# rpi5torpi4.net
KiCad netlist of a schematic drawn in EasyEDA Pro
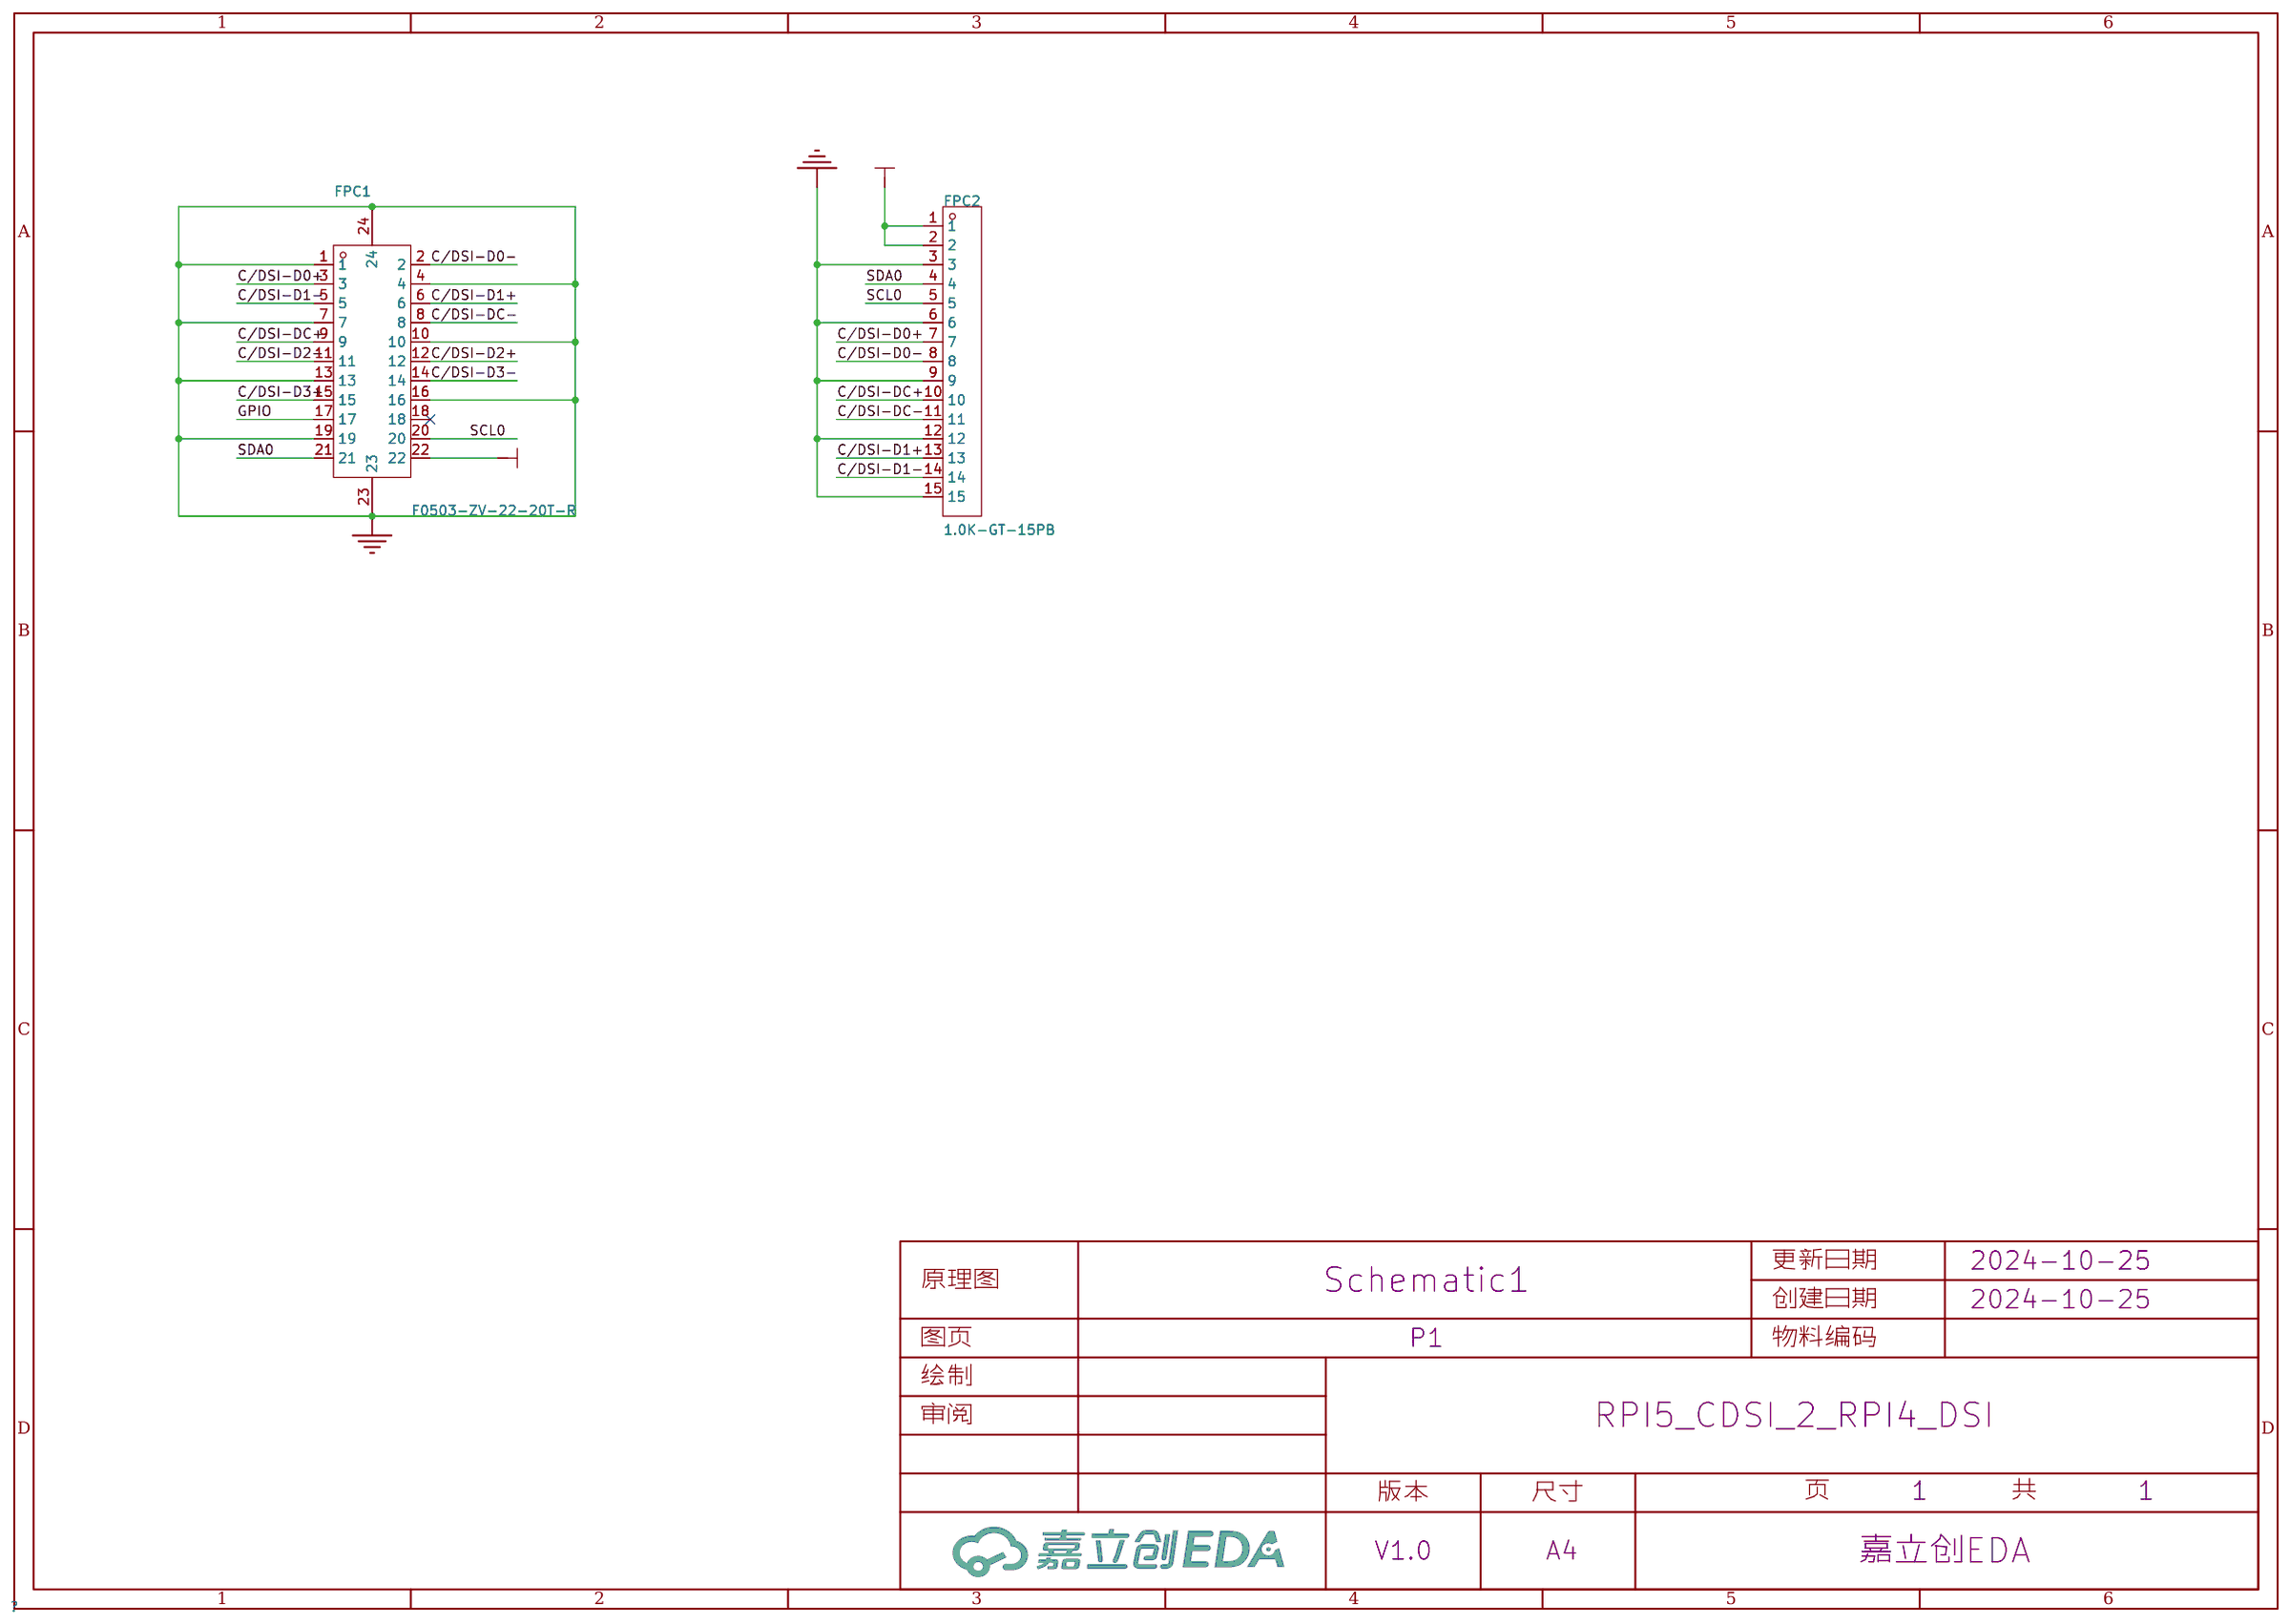
[diagram p0: schematic sheet]

(export (version "E")
  (design (tool "Eeschema 10.0.6"))
  (components
    (comp (ref "FPC1")
      (value "F0503-ZV-22-20T-R")
      (footprint "easyedapro:FPC-SMD_F0503-ZV-22-20T-R")
      (description "锁定特性:抽屉式;触点类型:单侧触点/垂直;触点数量:22P;间距:0.5mm;安装类型:立贴;")
      (fields (field (name "Manufacturer") "XFCN(兴飞)"))
      (libsource (lib "easyedapro") (part "F0503-ZV-22-20T-R"))
    )
    (comp (ref "FPC2")
      (value "1.0K-GT-15PB")
      (footprint "easyedapro:FPC-SMD_15P-P1.00_HDGC_1.0K-GT-15PB")
      (description "锁定特性:抽屉式;触点类型:单侧触点/垂直;触点数量:15P;间距:1mm;安装类型:立贴;工作温度范围:-20°C~+85°C;")
      (fields (field (name "Manufacturer") "HDGC(华德共创)"))
      (libsource (lib "easyedapro") (part "1.0K-GT-15PB"))
    )
  )
  (nets
    (net (code "1") (name "/C{slash}DSI-D0+") (class "Default")
      (node (ref "FPC1") (pin "3") (pinfunction "3_3") (pintype "unspecified"))
      (node (ref "FPC2") (pin "7") (pinfunction "7_7") (pintype "unspecified"))
    )
    (net (code "2") (name "/C{slash}DSI-D0-") (class "Default")
      (node (ref "FPC1") (pin "2") (pinfunction "2_2") (pintype "unspecified"))
      (node (ref "FPC2") (pin "8") (pinfunction "8_8") (pintype "unspecified"))
    )
    (net (code "3") (name "/C{slash}DSI-D1+") (class "Default")
      (node (ref "FPC1") (pin "6") (pinfunction "6_6") (pintype "unspecified"))
      (node (ref "FPC2") (pin "13") (pinfunction "13_13") (pintype "unspecified"))
    )
    (net (code "4") (name "/C{slash}DSI-D1-") (class "Default")
      (node (ref "FPC1") (pin "5") (pinfunction "5_5") (pintype "unspecified"))
      (node (ref "FPC2") (pin "14") (pinfunction "14_14") (pintype "unspecified"))
    )
    (net (code "5") (name "/C{slash}DSI-D2+") (class "Default")
      (node (ref "FPC1") (pin "12") (pinfunction "12_12") (pintype "unspecified"))
    )
    (net (code "6") (name "/C{slash}DSI-D2-") (class "Default")
      (node (ref "FPC1") (pin "11") (pinfunction "11_11") (pintype "unspecified"))
    )
    (net (code "7") (name "/C{slash}DSI-D3+") (class "Default")
      (node (ref "FPC1") (pin "15") (pinfunction "15_15") (pintype "unspecified"))
    )
    (net (code "8") (name "/C{slash}DSI-D3-") (class "Default")
      (node (ref "FPC1") (pin "14") (pinfunction "14_14") (pintype "unspecified"))
    )
    (net (code "9") (name "/C{slash}DSI-DC+") (class "Default")
      (node (ref "FPC1") (pin "9") (pinfunction "9_9") (pintype "unspecified"))
      (node (ref "FPC2") (pin "10") (pinfunction "10_10") (pintype "unspecified"))
    )
    (net (code "10") (name "/C{slash}DSI-DC-") (class "Default")
      (node (ref "FPC1") (pin "8") (pinfunction "8_8") (pintype "unspecified"))
      (node (ref "FPC2") (pin "11") (pinfunction "11_11") (pintype "unspecified"))
    )
    (net (code "11") (name "/GPIO") (class "Default")
      (node (ref "FPC1") (pin "17") (pinfunction "17_17") (pintype "unspecified"))
    )
    (net (code "12") (name "/SCL0") (class "Default")
      (node (ref "FPC1") (pin "20") (pinfunction "20_20") (pintype "unspecified"))
      (node (ref "FPC2") (pin "5") (pinfunction "5_5") (pintype "unspecified"))
    )
    (net (code "13") (name "/SDA0") (class "Default")
      (node (ref "FPC1") (pin "21") (pinfunction "21_21") (pintype "unspecified"))
      (node (ref "FPC2") (pin "4") (pinfunction "4_4") (pintype "unspecified"))
    )
    (net (code "14") (name "3V3") (class "Default")
      (node (ref "FPC1") (pin "22") (pinfunction "22_22") (pintype "unspecified"))
      (node (ref "FPC2") (pin "1") (pinfunction "1_1") (pintype "unspecified"))
      (node (ref "FPC2") (pin "2") (pinfunction "2_2") (pintype "unspecified"))
    )
    (net (code "15") (name "GND") (class "Default")
      (node (ref "FPC1") (pin "1") (pinfunction "1_1") (pintype "unspecified"))
      (node (ref "FPC1") (pin "10") (pinfunction "10_10") (pintype "unspecified"))
      (node (ref "FPC1") (pin "13") (pinfunction "13_13") (pintype "unspecified"))
      (node (ref "FPC1") (pin "16") (pinfunction "16_16") (pintype "unspecified"))
      (node (ref "FPC1") (pin "19") (pinfunction "19_19") (pintype "unspecified"))
      (node (ref "FPC1") (pin "23") (pinfunction "23_23") (pintype "unspecified"))
      (node (ref "FPC1") (pin "24") (pinfunction "24_24") (pintype "unspecified"))
      (node (ref "FPC1") (pin "4") (pinfunction "4_4") (pintype "unspecified"))
      (node (ref "FPC1") (pin "7") (pinfunction "7_7") (pintype "unspecified"))
      (node (ref "FPC2") (pin "12") (pinfunction "12_12") (pintype "unspecified"))
      (node (ref "FPC2") (pin "15") (pinfunction "15_15") (pintype "unspecified"))
      (node (ref "FPC2") (pin "3") (pinfunction "3_3") (pintype "unspecified"))
      (node (ref "FPC2") (pin "6") (pinfunction "6_6") (pintype "unspecified"))
      (node (ref "FPC2") (pin "9") (pinfunction "9_9") (pintype "unspecified"))
    )
    (net (code "16") (name "unconnected-(FPC1-Pad18)") (class "Default")
      (node (ref "FPC1") (pin "18") (pinfunction "18_18") (pintype "unspecified+no_connect"))
    )
  )
)
